# Phi.net
KiCad netlist of a schematic drawn in EAGLE
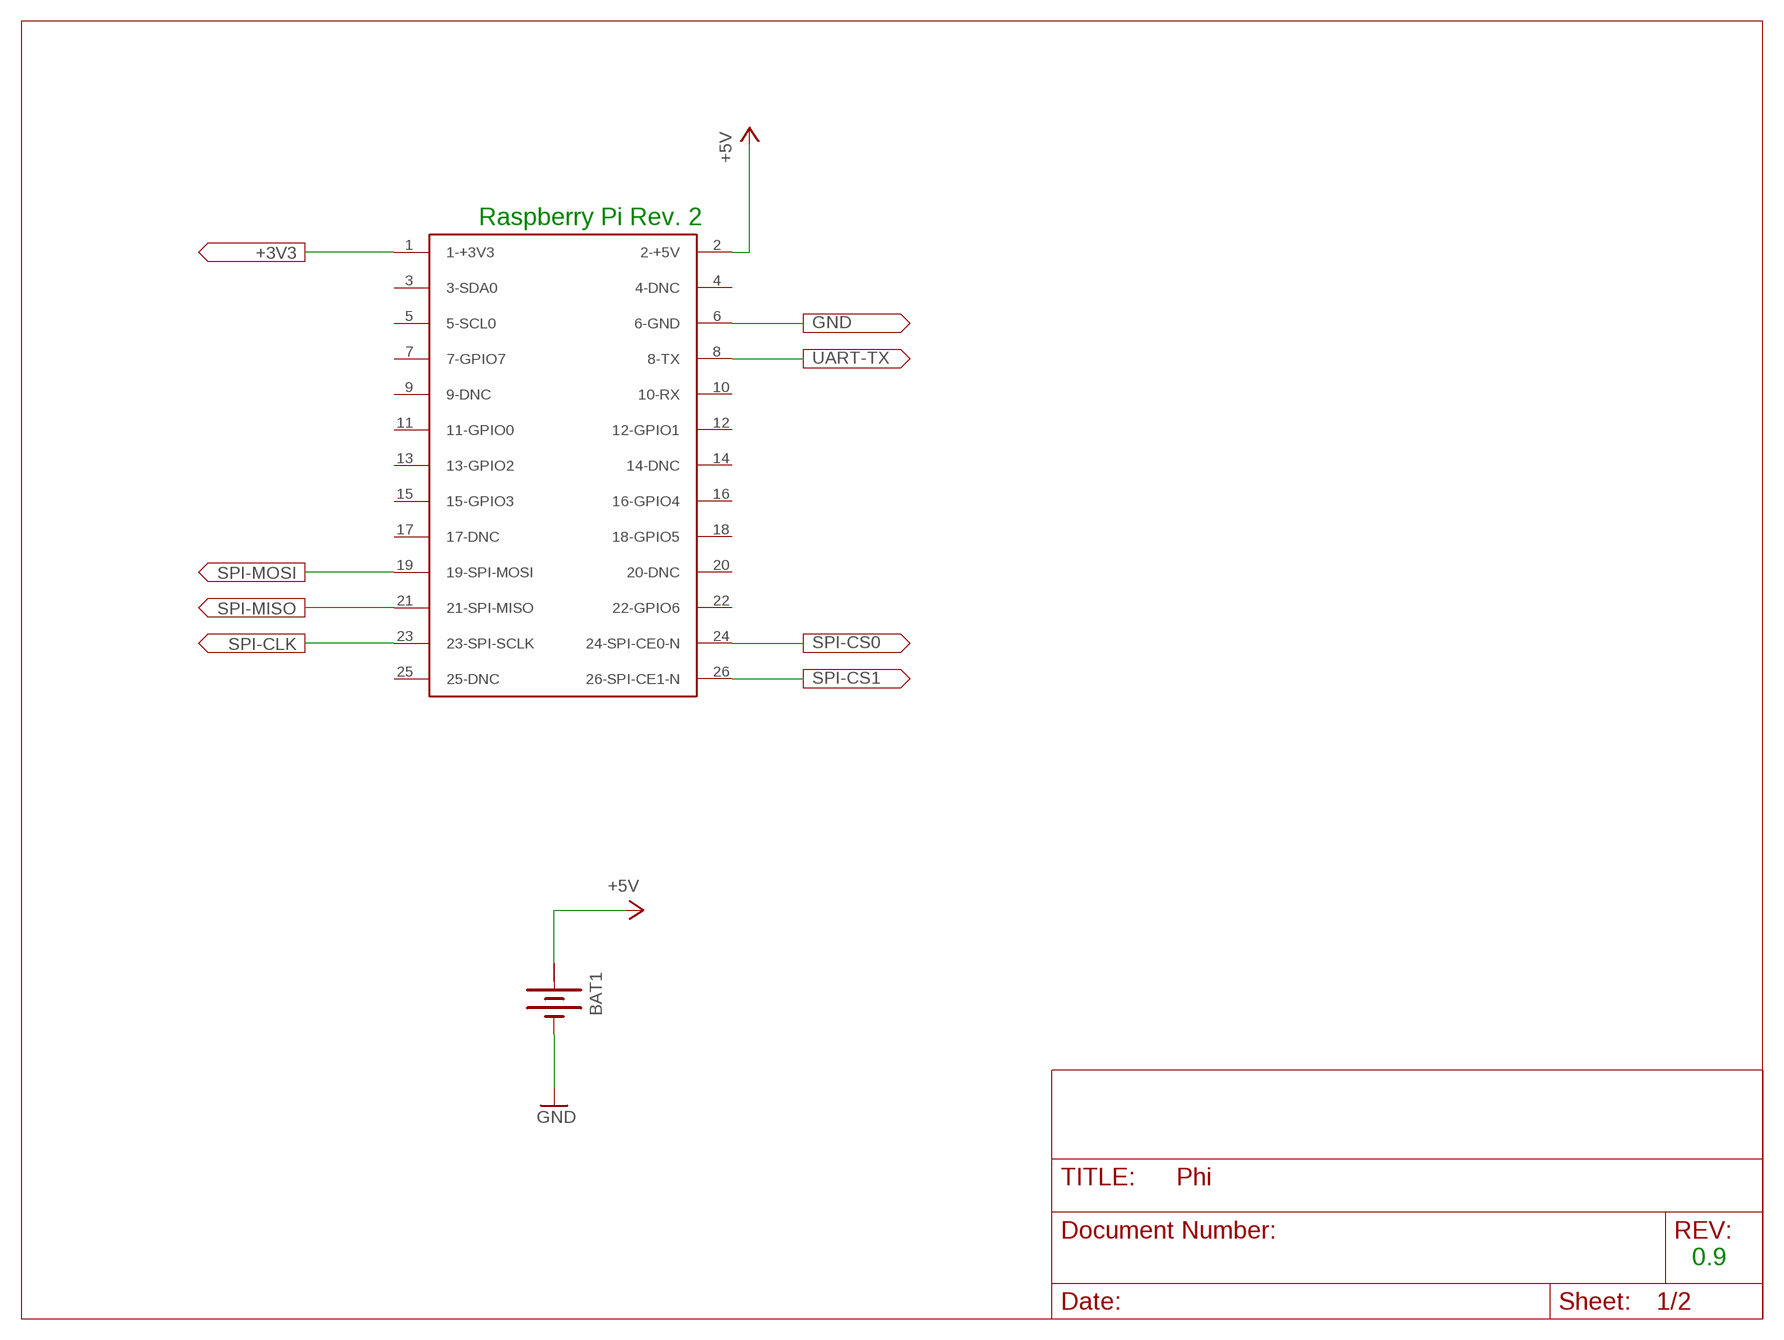
[diagram p0: schematic, sheet 1]
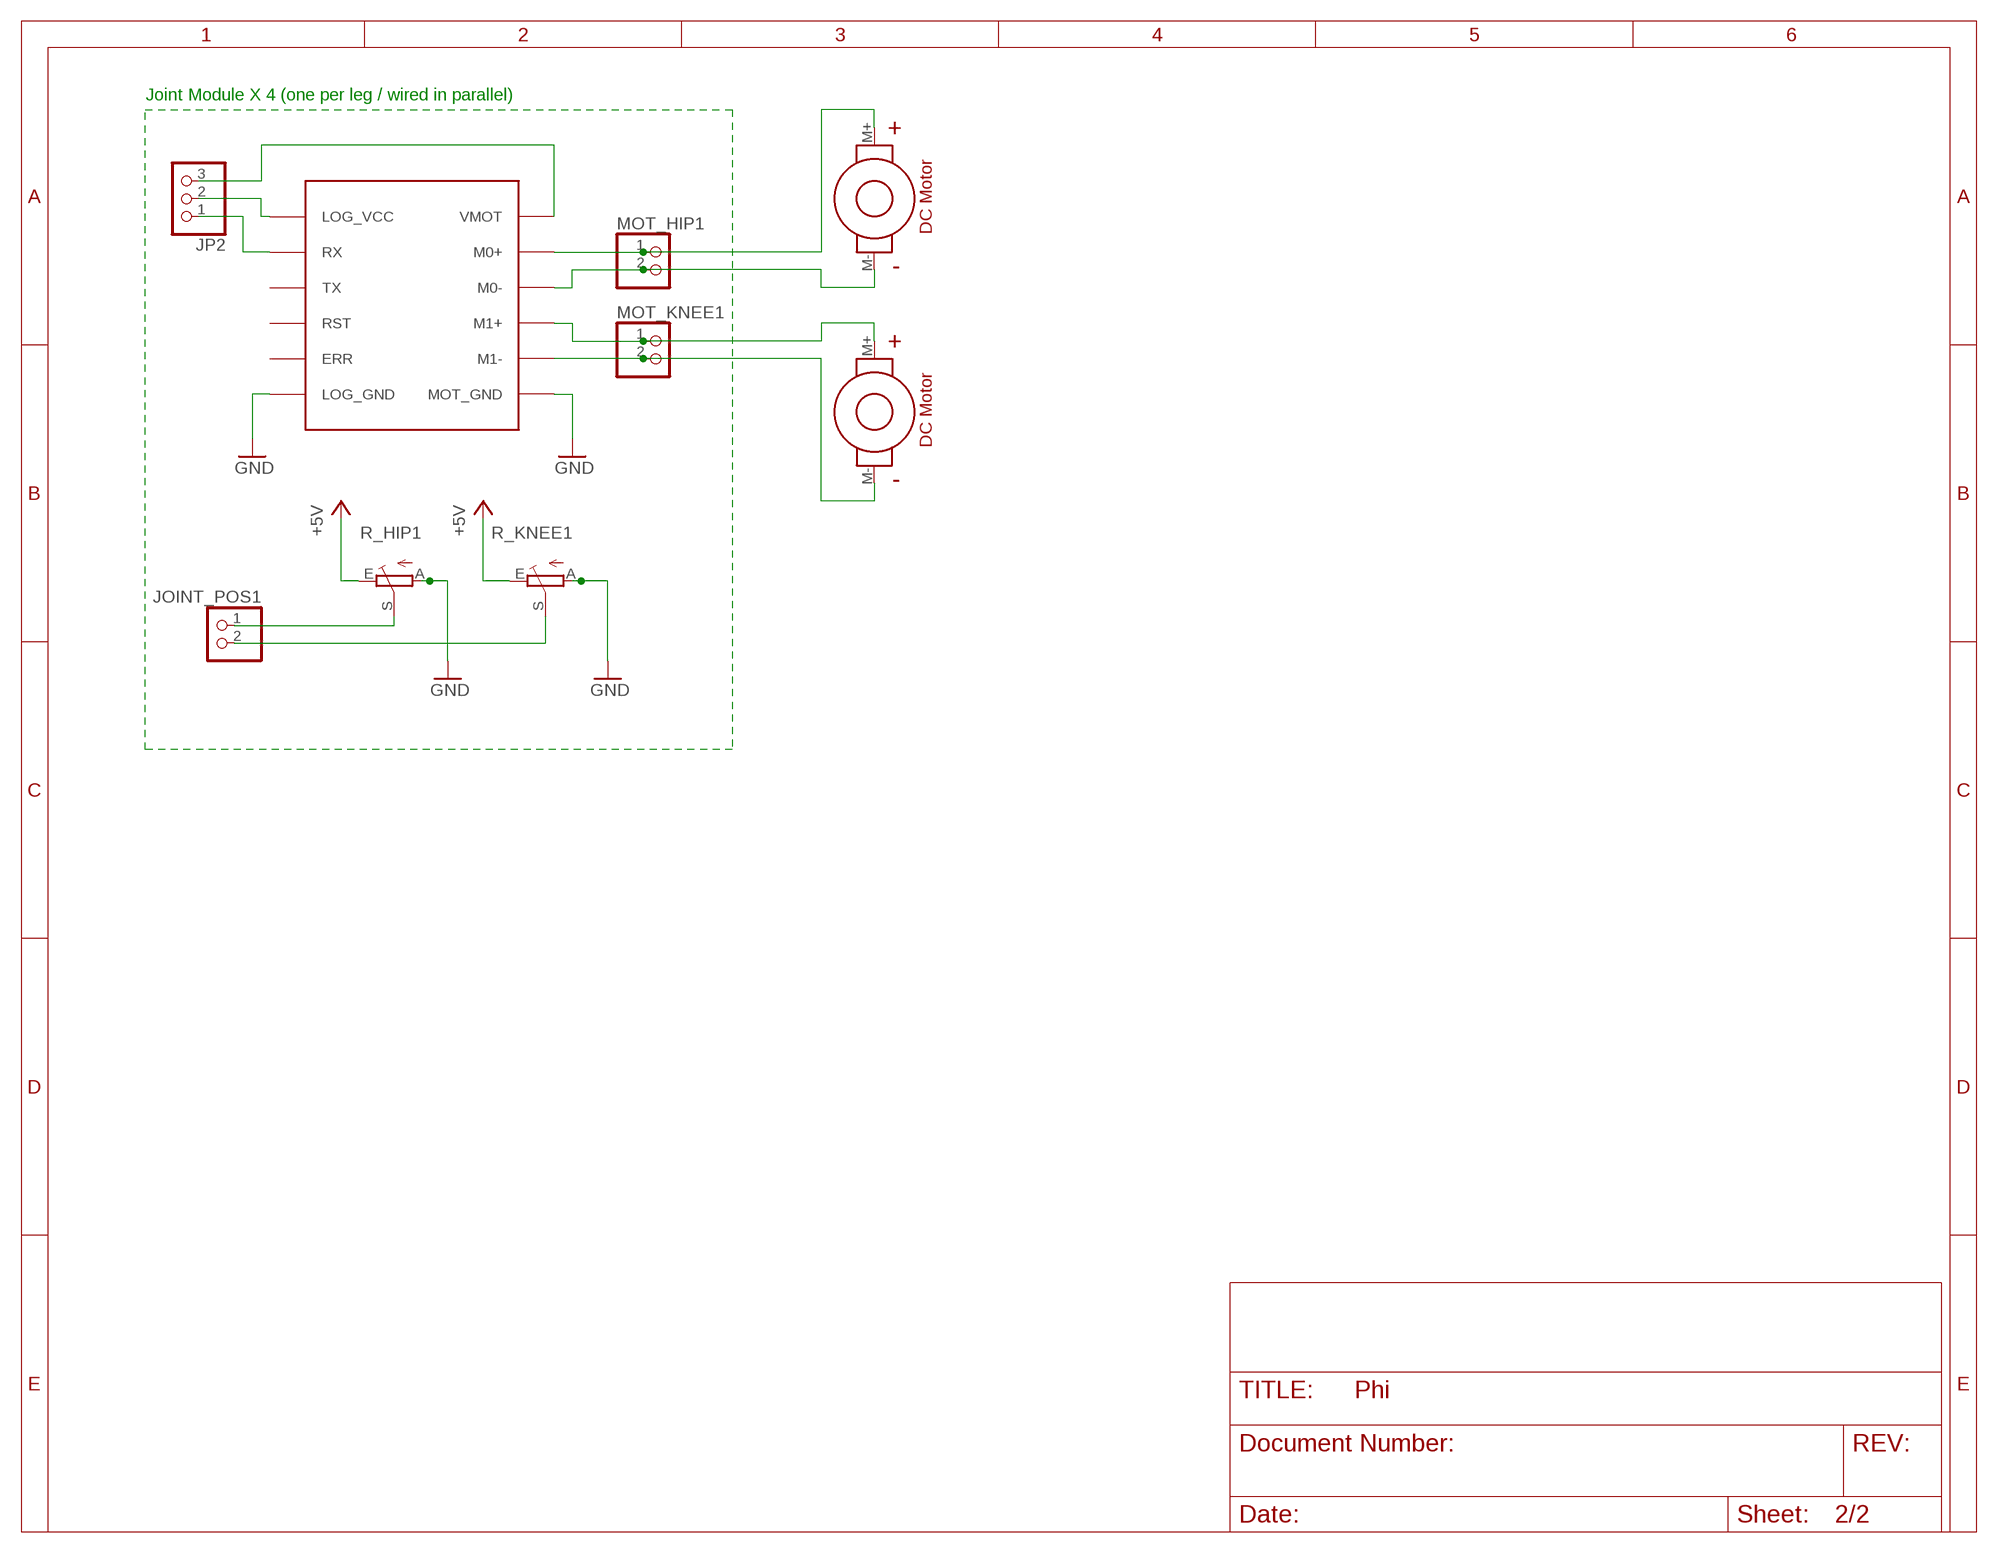
[diagram p1: schematic, sheet 2]

(export (version "E")
  (design (tool "Eeschema 10.0.6"))
  (components
    (comp (ref "BAT1")
      (value "BATTERY")
      (footprint "eagle-import:BATTERY")
      (libsource (lib "eagle-import") (part "BATTERY"))
    )
    (comp (ref "U$1")
      (value "RASPBERRY-PI")
      (footprint "eagle-import:RASPBERRY-PI")
      (libsource (lib "eagle-import") (part "RASPBERRY-PI"))
    )
    (comp (ref "JOINT_POS1")
      (value "PINHD-1X2")
      (footprint "eagle-import:1X02")
      (libsource (lib "eagle-import") (part "PINHD-1X2"))
    )
    (comp (ref "JP2")
      (value "PINHD-1X3")
      (footprint "eagle-import:1X03")
      (libsource (lib "eagle-import") (part "PINHD-1X3"))
    )
    (comp (ref "MOT_HIP1")
      (value "PINHD-1X2")
      (footprint "eagle-import:1X02")
      (libsource (lib "eagle-import") (part "PINHD-1X2"))
    )
    (comp (ref "MOT_KNEE1")
      (value "PINHD-1X2")
      (footprint "eagle-import:1X02")
      (libsource (lib "eagle-import") (part "PINHD-1X2"))
    )
    (comp (ref "R_HIP1")
      (value "TRIM_EU-B25P")
      (footprint "eagle-import:B25P")
      (libsource (lib "eagle-import") (part "TRIM_EU-B25P"))
    )
    (comp (ref "R_KNEE1")
      (value "TRIM_EU-B25P")
      (footprint "eagle-import:B25P")
      (libsource (lib "eagle-import") (part "TRIM_EU-B25P"))
    )
    (comp (ref "U$5")
      (value "QIK_2S9V1")
      (footprint "eagle-import:QIK_2S9V1_BOARD")
      (libsource (lib "eagle-import") (part "QIK_2S9V1"))
    )
    (comp (ref "U$6")
      (value "DC-MOTOR")
      (footprint "eagle-import:DC-MOTOR")
      (libsource (lib "eagle-import") (part "DC-MOTOR"))
    )
    (comp (ref "U$7")
      (value "DC-MOTOR")
      (footprint "eagle-import:DC-MOTOR")
      (libsource (lib "eagle-import") (part "DC-MOTOR"))
    )
  )
  (nets
    (net (code "1") (name "+") (class "Default")
      (node (ref "BAT1") (pin "+@1") (pinfunction "+_+@1") (pintype "power_in"))
    )
    (net (code "2") (name "+5V") (class "Default")
      (node (ref "BAT1") (pin "+") (pinfunction "+_+") (pintype "power_in"))
      (node (ref "JP2") (pin "3") (pinfunction "3_3") (pintype "passive"))
      (node (ref "R_HIP1") (pin "E") (pinfunction "E_E") (pintype "passive"))
      (node (ref "R_KNEE1") (pin "E") (pinfunction "E_E") (pintype "passive"))
      (node (ref "U$1") (pin "2") (pinfunction "2-+5V_2") (pintype "bidirectional"))
      (node (ref "U$5") (pin "VMOT") (pinfunction "VMOT_VMOT") (pintype "bidirectional"))
    )
    (net (code "3") (name "GND") (class "Default")
      (node (ref "BAT1") (pin "-") (pinfunction "-_-") (pintype "power_in"))
      (node (ref "R_HIP1") (pin "A") (pinfunction "A_A") (pintype "passive"))
      (node (ref "R_KNEE1") (pin "A") (pinfunction "A_A") (pintype "passive"))
      (node (ref "U$5") (pin "GND") (pinfunction "LOG_GND_GND") (pintype "bidirectional"))
      (node (ref "U$5") (pin "GND2") (pinfunction "MOT_GND_GND2") (pintype "bidirectional"))
    )
    (net (code "4") (name "Net-(JOINT_POS1-Pad1)") (class "Default")
      (node (ref "JOINT_POS1") (pin "1") (pinfunction "1_1") (pintype "passive"))
      (node (ref "R_HIP1") (pin "S") (pinfunction "S_S") (pintype "passive"))
    )
    (net (code "5") (name "Net-(JOINT_POS1-Pad2)") (class "Default")
      (node (ref "JOINT_POS1") (pin "2") (pinfunction "2_2") (pintype "passive"))
      (node (ref "R_KNEE1") (pin "S") (pinfunction "S_S") (pintype "passive"))
    )
    (net (code "6") (name "Net-(JP2-Pad1)") (class "Default")
      (node (ref "JP2") (pin "1") (pinfunction "1_1") (pintype "passive"))
      (node (ref "U$5") (pin "RX") (pinfunction "RX_RX") (pintype "bidirectional"))
    )
    (net (code "7") (name "Net-(MOT_HIP1-Pad1)") (class "Default")
      (node (ref "MOT_HIP1") (pin "1") (pinfunction "1_1") (pintype "passive"))
      (node (ref "U$5") (pin "M0+") (pinfunction "M0+_M0+") (pintype "bidirectional"))
      (node (ref "U$6") (pin "M+") (pinfunction "M+_M+") (pintype "bidirectional"))
    )
    (net (code "8") (name "Net-(MOT_HIP1-Pad2)") (class "Default")
      (node (ref "MOT_HIP1") (pin "2") (pinfunction "2_2") (pintype "passive"))
      (node (ref "U$5") (pin "M0-") (pinfunction "M0-_M0-") (pintype "bidirectional"))
      (node (ref "U$6") (pin "M-") (pinfunction "M-_M-") (pintype "bidirectional"))
    )
    (net (code "9") (name "Net-(MOT_KNEE1-Pad1)") (class "Default")
      (node (ref "MOT_KNEE1") (pin "1") (pinfunction "1_1") (pintype "passive"))
      (node (ref "U$5") (pin "M1+") (pinfunction "M1+_M1+") (pintype "bidirectional"))
      (node (ref "U$7") (pin "M+") (pinfunction "M+_M+") (pintype "bidirectional"))
    )
    (net (code "10") (name "Net-(MOT_KNEE1-Pad2)") (class "Default")
      (node (ref "MOT_KNEE1") (pin "2") (pinfunction "2_2") (pintype "passive"))
      (node (ref "U$5") (pin "M1-") (pinfunction "M1-_M1-") (pintype "bidirectional"))
      (node (ref "U$7") (pin "M-") (pinfunction "M-_M-") (pintype "bidirectional"))
    )
    (net (code "11") (name "Net-(U$5-LOG_VCC)") (class "Default")
      (node (ref "JP2") (pin "2") (pinfunction "2_2") (pintype "passive"))
      (node (ref "U$5") (pin "VCC") (pinfunction "LOG_VCC_VCC") (pintype "bidirectional"))
    )
    (net (code "12") (name "unconnected-(U$1-1-+3V3-Pad1)") (class "Default")
      (node (ref "U$1") (pin "1") (pinfunction "1-+3V3_1") (pintype "bidirectional"))
    )
    (net (code "13") (name "unconnected-(U$1-3-SDA0-Pad3)") (class "Default")
      (node (ref "U$1") (pin "3") (pinfunction "3-SDA0_3") (pintype "bidirectional"))
    )
    (net (code "14") (name "unconnected-(U$1-4-DNC-Pad4)") (class "Default")
      (node (ref "U$1") (pin "4") (pinfunction "4-DNC_4") (pintype "bidirectional"))
    )
    (net (code "15") (name "unconnected-(U$1-5-SCL0-Pad5)") (class "Default")
      (node (ref "U$1") (pin "5") (pinfunction "5-SCL0_5") (pintype "bidirectional"))
    )
    (net (code "16") (name "unconnected-(U$1-6-GND-Pad6)") (class "Default")
      (node (ref "U$1") (pin "6") (pinfunction "6-GND_6") (pintype "bidirectional"))
    )
    (net (code "17") (name "unconnected-(U$1-7-GPIO7-Pad7)") (class "Default")
      (node (ref "U$1") (pin "7") (pinfunction "7-GPIO7_7") (pintype "bidirectional"))
    )
    (net (code "18") (name "unconnected-(U$1-8-TX-Pad8)") (class "Default")
      (node (ref "U$1") (pin "8") (pinfunction "8-TX_8") (pintype "bidirectional"))
    )
    (net (code "19") (name "unconnected-(U$1-9-DNC-Pad9)") (class "Default")
      (node (ref "U$1") (pin "9") (pinfunction "9-DNC_9") (pintype "bidirectional"))
    )
    (net (code "20") (name "unconnected-(U$1-10-RX-Pad10)") (class "Default")
      (node (ref "U$1") (pin "10") (pinfunction "10-RX_10") (pintype "bidirectional"))
    )
    (net (code "21") (name "unconnected-(U$1-11-GPIO0-Pad11)") (class "Default")
      (node (ref "U$1") (pin "11") (pinfunction "11-GPIO0_11") (pintype "bidirectional"))
    )
    (net (code "22") (name "unconnected-(U$1-12-GPIO1-Pad12)") (class "Default")
      (node (ref "U$1") (pin "12") (pinfunction "12-GPIO1_12") (pintype "bidirectional"))
    )
    (net (code "23") (name "unconnected-(U$1-13-GPIO2-Pad13)") (class "Default")
      (node (ref "U$1") (pin "13") (pinfunction "13-GPIO2_13") (pintype "bidirectional"))
    )
    (net (code "24") (name "unconnected-(U$1-14-DNC-Pad14)") (class "Default")
      (node (ref "U$1") (pin "14") (pinfunction "14-DNC_14") (pintype "bidirectional"))
    )
    (net (code "25") (name "unconnected-(U$1-15-GPIO3-Pad15)") (class "Default")
      (node (ref "U$1") (pin "15") (pinfunction "15-GPIO3_15") (pintype "bidirectional"))
    )
    (net (code "26") (name "unconnected-(U$1-16-GPIO4-Pad16)") (class "Default")
      (node (ref "U$1") (pin "16") (pinfunction "16-GPIO4_16") (pintype "bidirectional"))
    )
    (net (code "27") (name "unconnected-(U$1-17-DNC-Pad17)") (class "Default")
      (node (ref "U$1") (pin "17") (pinfunction "17-DNC_17") (pintype "bidirectional"))
    )
    (net (code "28") (name "unconnected-(U$1-18-GPIO5-Pad18)") (class "Default")
      (node (ref "U$1") (pin "18") (pinfunction "18-GPIO5_18") (pintype "bidirectional"))
    )
    (net (code "29") (name "unconnected-(U$1-19-SPI-MOSI-Pad19)") (class "Default")
      (node (ref "U$1") (pin "19") (pinfunction "19-SPI-MOSI_19") (pintype "bidirectional"))
    )
    (net (code "30") (name "unconnected-(U$1-20-DNC-Pad20)") (class "Default")
      (node (ref "U$1") (pin "20") (pinfunction "20-DNC_20") (pintype "bidirectional"))
    )
    (net (code "31") (name "unconnected-(U$1-21-SPI-MISO-Pad21)") (class "Default")
      (node (ref "U$1") (pin "21") (pinfunction "21-SPI-MISO_21") (pintype "bidirectional"))
    )
    (net (code "32") (name "unconnected-(U$1-22-GPIO6-Pad22)") (class "Default")
      (node (ref "U$1") (pin "22") (pinfunction "22-GPIO6_22") (pintype "bidirectional"))
    )
    (net (code "33") (name "unconnected-(U$1-23-SPI-SCLK-Pad23)") (class "Default")
      (node (ref "U$1") (pin "23") (pinfunction "23-SPI-SCLK_23") (pintype "bidirectional"))
    )
    (net (code "34") (name "unconnected-(U$1-24-SPI-CE0-N-Pad24)") (class "Default")
      (node (ref "U$1") (pin "24") (pinfunction "24-SPI-CE0-N_24") (pintype "bidirectional"))
    )
    (net (code "35") (name "unconnected-(U$1-25-DNC-Pad25)") (class "Default")
      (node (ref "U$1") (pin "25") (pinfunction "25-DNC_25") (pintype "bidirectional"))
    )
    (net (code "36") (name "unconnected-(U$1-26-SPI-CE1-N-Pad26)") (class "Default")
      (node (ref "U$1") (pin "26") (pinfunction "26-SPI-CE1-N_26") (pintype "bidirectional"))
    )
    (net (code "37") (name "unconnected-(U$5-PadERR)") (class "Default")
      (node (ref "U$5") (pin "ERR") (pinfunction "ERR_ERR") (pintype "bidirectional"))
    )
    (net (code "38") (name "unconnected-(U$5-PadRST)") (class "Default")
      (node (ref "U$5") (pin "RST") (pinfunction "RST_RST") (pintype "bidirectional"))
    )
    (net (code "39") (name "unconnected-(U$5-PadTX)") (class "Default")
      (node (ref "U$5") (pin "TX") (pinfunction "TX_TX") (pintype "bidirectional"))
    )
  )
)
